# SCH_angle-sensor_2024-07-24.net
KiCad netlist of a schematic drawn in EasyEDA
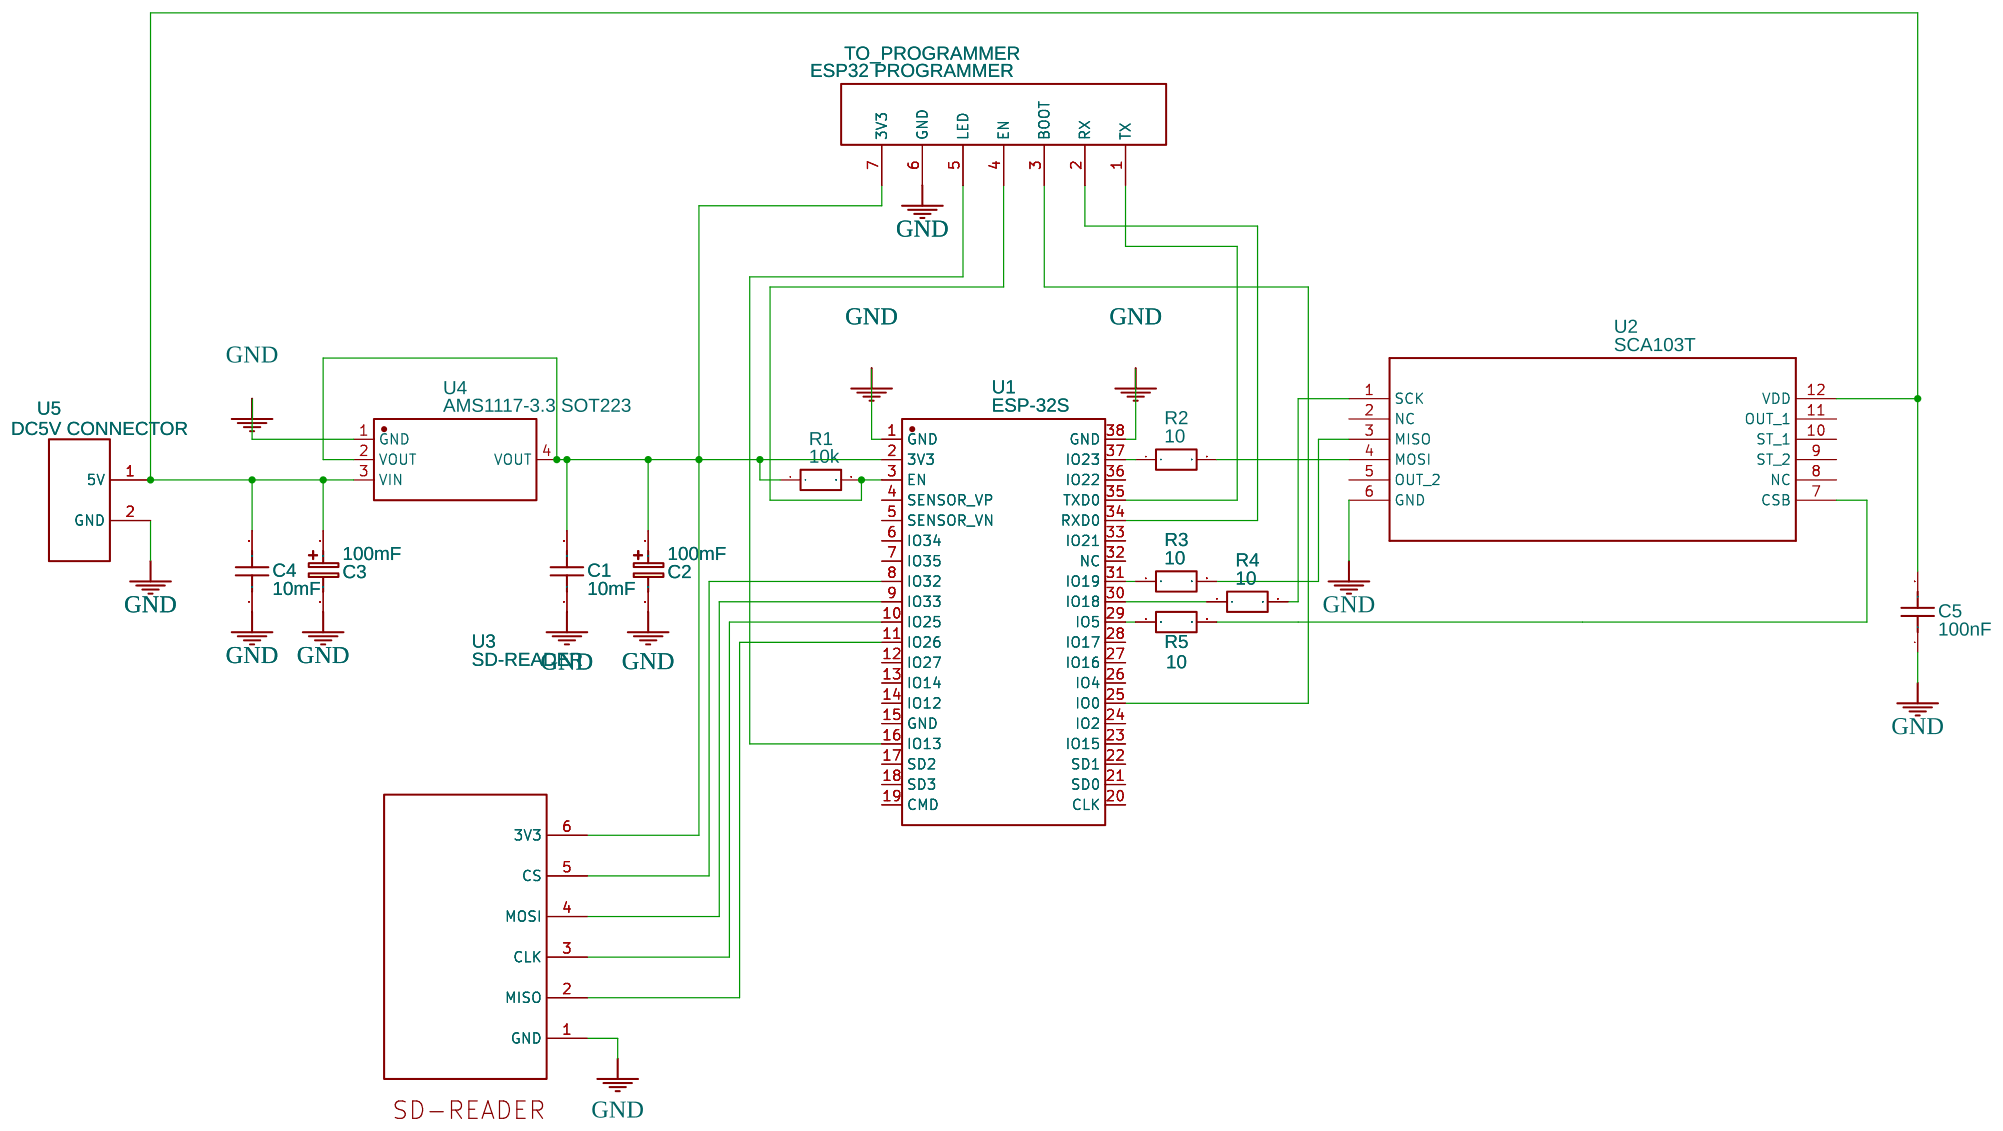
[diagram p0: schematic sheet]

(export (version "E")
  (design (tool "Eeschema 10.0.6"))
  (components
    (comp (ref "C1") (value "10mF") (libsource (lib "") (part "C_0603_US")))
    (comp (ref "C2") (value "100mF") (libsource (lib "") (part "C_Tan_SMD_A_EU_1")))
    (comp (ref "C3") (value "100mF") (libsource (lib "") (part "C_Tan_SMD_A_EU")))
    (comp (ref "C4") (value "10mF") (libsource (lib "") (part "C_0603_US")))
    (comp (ref "C5") (value "100nF") (libsource (lib "") (part "C_0603_US")))
    (comp (ref "R1") (value "10k") (libsource (lib "") (part "R_0603_EU")))
    (comp (ref "R2") (value "10") (libsource (lib "") (part "R_0603_EU")))
    (comp (ref "R3") (value "10") (libsource (lib "") (part "R_0603_EU")))
    (comp (ref "R4") (value "10") (libsource (lib "") (part "R_0603_EU")))
    (comp (ref "R5") (value "10") (libsource (lib "") (part "R_0603_EU")))
    (comp (ref "TO_PROGRAMMER") (value "ESP32 PROGRAMMER") (libsource (lib "") (part "ESP32 PROGRAMMER")))
    (comp (ref "U1") (value "ESP-32S") (libsource (lib "") (part "ESP-32S")))
    (comp (ref "U2") (value "SCA103T") (libsource (lib "") (part "SCA103T")))
    (comp (ref "U3") (value "SD-READER") (libsource (lib "") (part "SD-READER")))
    (comp (ref "U4") (value "AMS1117-3.3 SOT223") (libsource (lib "") (part "AMS1117-3.3 SOT223")))
    (comp (ref "U5") (value "DC5V CONNECTOR") (libsource (lib "") (part "DC5V CONNECTOR")))
  )
  (nets
    (net (code "1") (name "GND") (class "Default")
      (node (ref "C1") (pin "1") (pinfunction "1_1") (pintype "unspecified"))
      (node (ref "C2") (pin "2") (pinfunction "2_2") (pintype "unspecified"))
      (node (ref "C3") (pin "2") (pinfunction "2_2") (pintype "unspecified"))
      (node (ref "C4") (pin "1") (pinfunction "1_1") (pintype "unspecified"))
      (node (ref "C5") (pin "1") (pinfunction "1_1") (pintype "unspecified"))
      (node (ref "TO_PROGRAMMER") (pin "6") (pinfunction "GND_6") (pintype "unspecified"))
      (node (ref "U1") (pin "1") (pinfunction "GND_1") (pintype "unspecified"))
      (node (ref "U1") (pin "38") (pinfunction "GND_38") (pintype "unspecified"))
      (node (ref "U2") (pin "6") (pinfunction "GND_6") (pintype "passive"))
      (node (ref "U3") (pin "1") (pinfunction "GND_1") (pintype "unspecified"))
      (node (ref "U4") (pin "1") (pinfunction "GND_1") (pintype "unspecified"))
      (node (ref "U5") (pin "2") (pinfunction "GND_2") (pintype "unspecified"))
    )
    (net (code "2") (name "Net-(TO_PROGRAMMER-3V3)") (class "Default")
      (node (ref "C1") (pin "2") (pinfunction "2_2") (pintype "unspecified"))
      (node (ref "C2") (pin "1") (pinfunction "1_1") (pintype "unspecified"))
      (node (ref "R1") (pin "1") (pinfunction "1_1") (pintype "unspecified"))
      (node (ref "TO_PROGRAMMER") (pin "7") (pinfunction "3V3_7") (pintype "unspecified"))
      (node (ref "U1") (pin "2") (pinfunction "3V3_2") (pintype "unspecified"))
      (node (ref "U3") (pin "6") (pinfunction "3V3_6") (pintype "unspecified"))
      (node (ref "U4") (pin "2") (pinfunction "VOUT_2") (pintype "unspecified"))
      (node (ref "U4") (pin "4") (pinfunction "VOUT_4") (pintype "unspecified"))
    )
    (net (code "3") (name "Net-(TO_PROGRAMMER-BOOT)") (class "Default")
      (node (ref "TO_PROGRAMMER") (pin "3") (pinfunction "BOOT_3") (pintype "unspecified"))
      (node (ref "U1") (pin "25") (pinfunction "IO0_25") (pintype "unspecified"))
    )
    (net (code "4") (name "Net-(TO_PROGRAMMER-EN)") (class "Default")
      (node (ref "R1") (pin "2") (pinfunction "2_2") (pintype "unspecified"))
      (node (ref "TO_PROGRAMMER") (pin "4") (pinfunction "EN_4") (pintype "unspecified"))
      (node (ref "U1") (pin "3") (pinfunction "EN_3") (pintype "unspecified"))
    )
    (net (code "5") (name "Net-(TO_PROGRAMMER-LED)") (class "Default")
      (node (ref "TO_PROGRAMMER") (pin "5") (pinfunction "LED_5") (pintype "unspecified"))
      (node (ref "U1") (pin "16") (pinfunction "IO13_16") (pintype "unspecified"))
    )
    (net (code "6") (name "Net-(TO_PROGRAMMER-RX)") (class "Default")
      (node (ref "TO_PROGRAMMER") (pin "2") (pinfunction "RX_2") (pintype "unspecified"))
      (node (ref "U1") (pin "34") (pinfunction "RXD0_34") (pintype "unspecified"))
    )
    (net (code "7") (name "Net-(TO_PROGRAMMER-TX)") (class "Default")
      (node (ref "TO_PROGRAMMER") (pin "1") (pinfunction "TX_1") (pintype "unspecified"))
      (node (ref "U1") (pin "35") (pinfunction "TXD0_35") (pintype "unspecified"))
    )
    (net (code "8") (name "Net-(U1-IO5)") (class "Default")
      (node (ref "R5") (pin "1") (pinfunction "1_1") (pintype "unspecified"))
      (node (ref "U1") (pin "29") (pinfunction "IO5_29") (pintype "unspecified"))
    )
    (net (code "9") (name "Net-(U1-IO18)") (class "Default")
      (node (ref "R4") (pin "1") (pinfunction "1_1") (pintype "unspecified"))
      (node (ref "U1") (pin "30") (pinfunction "IO18_30") (pintype "unspecified"))
    )
    (net (code "10") (name "Net-(U1-IO19)") (class "Default")
      (node (ref "R3") (pin "1") (pinfunction "1_1") (pintype "unspecified"))
      (node (ref "U1") (pin "31") (pinfunction "IO19_31") (pintype "unspecified"))
    )
    (net (code "11") (name "Net-(U1-IO23)") (class "Default")
      (node (ref "R2") (pin "1") (pinfunction "1_1") (pintype "unspecified"))
      (node (ref "U1") (pin "37") (pinfunction "IO23_37") (pintype "unspecified"))
    )
    (net (code "12") (name "Net-(U1-IO25)") (class "Default")
      (node (ref "U1") (pin "10") (pinfunction "IO25_10") (pintype "unspecified"))
      (node (ref "U3") (pin "3") (pinfunction "CLK_3") (pintype "unspecified"))
    )
    (net (code "13") (name "Net-(U1-IO26)") (class "Default")
      (node (ref "U1") (pin "11") (pinfunction "IO26_11") (pintype "unspecified"))
      (node (ref "U3") (pin "2") (pinfunction "MISO_2") (pintype "unspecified"))
    )
    (net (code "14") (name "Net-(U1-IO32)") (class "Default")
      (node (ref "U1") (pin "8") (pinfunction "IO32_8") (pintype "unspecified"))
      (node (ref "U3") (pin "5") (pinfunction "CS_5") (pintype "unspecified"))
    )
    (net (code "15") (name "Net-(U1-IO33)") (class "Default")
      (node (ref "U1") (pin "9") (pinfunction "IO33_9") (pintype "unspecified"))
      (node (ref "U3") (pin "4") (pinfunction "MOSI_4") (pintype "unspecified"))
    )
    (net (code "16") (name "Net-(U2-CSB)") (class "Default")
      (node (ref "R5") (pin "2") (pinfunction "2_2") (pintype "unspecified"))
      (node (ref "U2") (pin "7") (pinfunction "CSB_7") (pintype "input"))
    )
    (net (code "17") (name "Net-(U2-MISO)") (class "Default")
      (node (ref "R3") (pin "2") (pinfunction "2_2") (pintype "unspecified"))
      (node (ref "U2") (pin "3") (pinfunction "MISO_3") (pintype "output"))
    )
    (net (code "18") (name "Net-(U2-MOSI)") (class "Default")
      (node (ref "R2") (pin "2") (pinfunction "2_2") (pintype "unspecified"))
      (node (ref "U2") (pin "4") (pinfunction "MOSI_4") (pintype "input"))
    )
    (net (code "19") (name "Net-(U2-SCK)") (class "Default")
      (node (ref "R4") (pin "2") (pinfunction "2_2") (pintype "unspecified"))
      (node (ref "U2") (pin "1") (pinfunction "SCK_1") (pintype "input"))
    )
    (net (code "20") (name "Net-(U2-VDD)") (class "Default")
      (node (ref "C3") (pin "1") (pinfunction "1_1") (pintype "unspecified"))
      (node (ref "C4") (pin "2") (pinfunction "2_2") (pintype "unspecified"))
      (node (ref "C5") (pin "2") (pinfunction "2_2") (pintype "unspecified"))
      (node (ref "U2") (pin "12") (pinfunction "VDD_12") (pintype "passive"))
      (node (ref "U4") (pin "3") (pinfunction "VIN_3") (pintype "unspecified"))
      (node (ref "U5") (pin "1") (pinfunction "5V_1") (pintype "unspecified"))
    )
    (net (code "21") (name "unconnected-(U1-CLK-Pad20)") (class "Default")
      (node (ref "U1") (pin "20") (pinfunction "CLK_20") (pintype "unspecified"))
    )
    (net (code "22") (name "unconnected-(U1-CMD-Pad19)") (class "Default")
      (node (ref "U1") (pin "19") (pinfunction "CMD_19") (pintype "unspecified"))
    )
    (net (code "23") (name "unconnected-(U1-GND-Pad15)") (class "Default")
      (node (ref "U1") (pin "15") (pinfunction "GND_15") (pintype "unspecified"))
    )
    (net (code "24") (name "unconnected-(U1-IO2-Pad24)") (class "Default")
      (node (ref "U1") (pin "24") (pinfunction "IO2_24") (pintype "unspecified"))
    )
    (net (code "25") (name "unconnected-(U1-IO4-Pad26)") (class "Default")
      (node (ref "U1") (pin "26") (pinfunction "IO4_26") (pintype "unspecified"))
    )
    (net (code "26") (name "unconnected-(U1-IO12-Pad14)") (class "Default")
      (node (ref "U1") (pin "14") (pinfunction "IO12_14") (pintype "unspecified"))
    )
    (net (code "27") (name "unconnected-(U1-IO14-Pad13)") (class "Default")
      (node (ref "U1") (pin "13") (pinfunction "IO14_13") (pintype "unspecified"))
    )
    (net (code "28") (name "unconnected-(U1-IO15-Pad23)") (class "Default")
      (node (ref "U1") (pin "23") (pinfunction "IO15_23") (pintype "unspecified"))
    )
    (net (code "29") (name "unconnected-(U1-IO16-Pad27)") (class "Default")
      (node (ref "U1") (pin "27") (pinfunction "IO16_27") (pintype "unspecified"))
    )
    (net (code "30") (name "unconnected-(U1-IO17-Pad28)") (class "Default")
      (node (ref "U1") (pin "28") (pinfunction "IO17_28") (pintype "unspecified"))
    )
    (net (code "31") (name "unconnected-(U1-IO21-Pad33)") (class "Default")
      (node (ref "U1") (pin "33") (pinfunction "IO21_33") (pintype "unspecified"))
    )
    (net (code "32") (name "unconnected-(U1-IO22-Pad36)") (class "Default")
      (node (ref "U1") (pin "36") (pinfunction "IO22_36") (pintype "unspecified"))
    )
    (net (code "33") (name "unconnected-(U1-IO27-Pad12)") (class "Default")
      (node (ref "U1") (pin "12") (pinfunction "IO27_12") (pintype "unspecified"))
    )
    (net (code "34") (name "unconnected-(U1-IO34-Pad6)") (class "Default")
      (node (ref "U1") (pin "6") (pinfunction "IO34_6") (pintype "unspecified"))
    )
    (net (code "35") (name "unconnected-(U1-IO35-Pad7)") (class "Default")
      (node (ref "U1") (pin "7") (pinfunction "IO35_7") (pintype "unspecified"))
    )
    (net (code "36") (name "unconnected-(U1-NC-Pad32)") (class "Default")
      (node (ref "U1") (pin "32") (pinfunction "NC_32") (pintype "unspecified"))
    )
    (net (code "37") (name "unconnected-(U1-SD0-Pad21)") (class "Default")
      (node (ref "U1") (pin "21") (pinfunction "SD0_21") (pintype "unspecified"))
    )
    (net (code "38") (name "unconnected-(U1-SD1-Pad22)") (class "Default")
      (node (ref "U1") (pin "22") (pinfunction "SD1_22") (pintype "unspecified"))
    )
    (net (code "39") (name "unconnected-(U1-SD2-Pad17)") (class "Default")
      (node (ref "U1") (pin "17") (pinfunction "SD2_17") (pintype "unspecified"))
    )
    (net (code "40") (name "unconnected-(U1-SD3-Pad18)") (class "Default")
      (node (ref "U1") (pin "18") (pinfunction "SD3_18") (pintype "unspecified"))
    )
    (net (code "41") (name "unconnected-(U1-SENSOR_VN-Pad5)") (class "Default")
      (node (ref "U1") (pin "5") (pinfunction "SENSOR_VN_5") (pintype "unspecified"))
    )
    (net (code "42") (name "unconnected-(U1-SENSOR_VP-Pad4)") (class "Default")
      (node (ref "U1") (pin "4") (pinfunction "SENSOR_VP_4") (pintype "unspecified"))
    )
    (net (code "43") (name "unconnected-(U2-NC-Pad2)") (class "Default")
      (node (ref "U2") (pin "2") (pinfunction "NC_2") (pintype "unspecified"))
    )
    (net (code "44") (name "unconnected-(U2-NC-Pad8)") (class "Default")
      (node (ref "U2") (pin "8") (pinfunction "NC_8") (pintype "unspecified"))
    )
    (net (code "45") (name "unconnected-(U2-OUT_1-Pad11)") (class "Default")
      (node (ref "U2") (pin "11") (pinfunction "OUT_1_11") (pintype "output"))
    )
    (net (code "46") (name "unconnected-(U2-OUT_2-Pad5)") (class "Default")
      (node (ref "U2") (pin "5") (pinfunction "OUT_2_5") (pintype "output"))
    )
    (net (code "47") (name "unconnected-(U2-ST_1-Pad10)") (class "Default")
      (node (ref "U2") (pin "10") (pinfunction "ST_1_10") (pintype "input"))
    )
    (net (code "48") (name "unconnected-(U2-ST_2-Pad9)") (class "Default")
      (node (ref "U2") (pin "9") (pinfunction "ST_2_9") (pintype "input"))
    )
  )
)
